# bela_expansion_card_2.net
KiCad netlist of a schematic drawn in Altium Designer
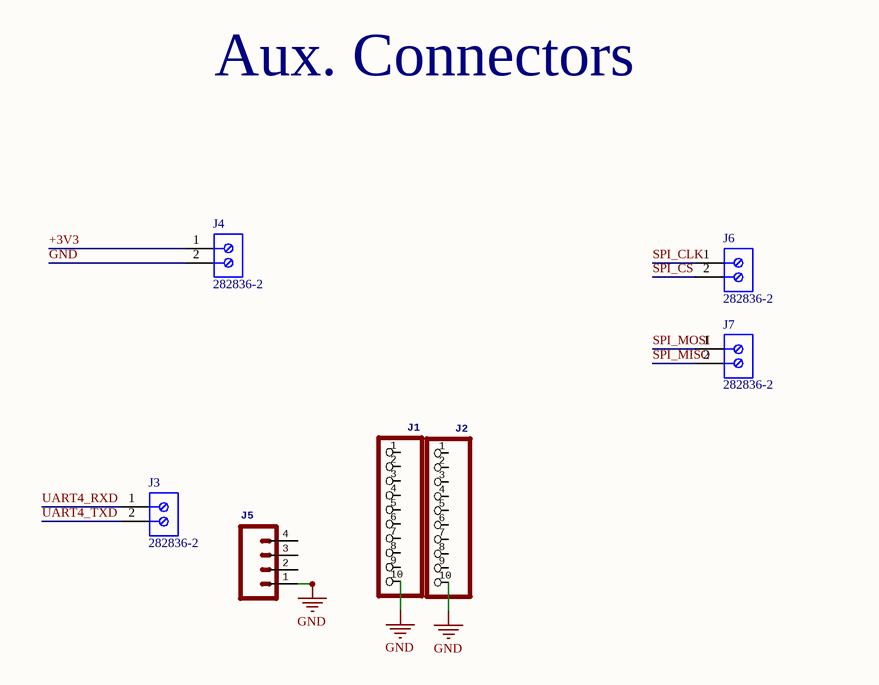
[diagram p0: bela_expansion_card_2.SchDoc]

(export (version "E")
  (design (tool "Eeschema 10.0.6"))
  (components
    (comp (ref "J1")
      (value "PINHD-1X10")
      (footprint "HDR1X10")
      (description "PIN HEADER")
      (fields (field (name "LIBRARYNAME") "pinhead"))
      (libsource (lib "pinhead") (part "PINHD-1X10"))
    )
    (comp (ref "J2")
      (value "PINHD-1X10")
      (footprint "HDR1X10")
      (description "PIN HEADER")
      (fields (field (name "LIBRARYNAME") "pinhead"))
      (libsource (lib "Miscellaneous Connectors") (part "PINHD-1X10"))
    )
    (comp (ref "J3")
      (value "282836-2")
      (footprint "TECO-282836-2_V")
      (description "Female Header, Pitch 5 mm, 1 x 2 Position, Height 10 mm, Tail Length 3.5 mm, Rohs, Bulk")
      (fields (field (name "VOLTAGE") "300V") (field (name "MANUFACTURER") "TE Connectivity"))
      (libsource (lib "Altium Content Vault") (part "CN-1P-F-TB2"))
    )
    (comp (ref "J4")
      (value "282836-2")
      (footprint "TECO-282836-2_V")
      (description "Female Header, Pitch 5 mm, 1 x 2 Position, Height 10 mm, Tail Length 3.5 mm, Rohs, Bulk")
      (fields (field (name "VOLTAGE") "300V") (field (name "MANUFACTURER") "TE Connectivity"))
      (libsource (lib "Altium Content Vault") (part "CN-1P-F-TB2"))
    )
    (comp (ref "J5")
      (value "M04PTH")
      (footprint "1X04")
      (libsource (lib "SparkFun-Connectors") (part "M04PTH"))
    )
    (comp (ref "J6")
      (value "282836-2")
      (footprint "TECO-282836-2_V")
      (description "Female Header, Pitch 5 mm, 1 x 2 Position, Height 10 mm, Tail Length 3.5 mm, Rohs, Bulk")
      (fields (field (name "VOLTAGE") "300V") (field (name "MANUFACTURER") "TE Connectivity"))
      (libsource (lib "Altium Content Vault") (part "CN-1P-F-TB2"))
    )
    (comp (ref "J7")
      (value "282836-2")
      (footprint "TECO-282836-2_V")
      (description "Female Header, Pitch 5 mm, 1 x 2 Position, Height 10 mm, Tail Length 3.5 mm, Rohs, Bulk")
      (fields (field (name "VOLTAGE") "300V") (field (name "MANUFACTURER") "TE Connectivity"))
      (libsource (lib "Altium Content Vault") (part "CN-1P-F-TB2"))
    )
  )
  (nets
    (net (code "1") (name "/+3V3") (class "Default")
      (node (ref "J4") (pin "1") (pinfunction "1_1") (pintype "passive"))
    )
    (net (code "2") (name "/SPI_CLK") (class "Default")
      (node (ref "J6") (pin "1") (pinfunction "1_1") (pintype "passive"))
    )
    (net (code "3") (name "/SPI_CS") (class "Default")
      (node (ref "J6") (pin "2") (pinfunction "2_2") (pintype "passive"))
    )
    (net (code "4") (name "/SPI_MISO") (class "Default")
      (node (ref "J7") (pin "2") (pinfunction "2_2") (pintype "passive"))
    )
    (net (code "5") (name "/SPI_MOSI") (class "Default")
      (node (ref "J7") (pin "1") (pinfunction "1_1") (pintype "passive"))
    )
    (net (code "6") (name "/UART4_RXD") (class "Default")
      (node (ref "J3") (pin "1") (pinfunction "1_1") (pintype "passive"))
    )
    (net (code "7") (name "/UART4_TXD") (class "Default")
      (node (ref "J3") (pin "2") (pinfunction "2_2") (pintype "passive"))
    )
    (net (code "8") (name "GND") (class "Default")
      (node (ref "J1") (pin "10") (pinfunction "10_10") (pintype "passive"))
      (node (ref "J2") (pin "10") (pinfunction "10_10") (pintype "passive"))
      (node (ref "J4") (pin "2") (pinfunction "2_2") (pintype "passive"))
      (node (ref "J5") (pin "1") (pinfunction "1_1") (pintype "passive"))
    )
    (net (code "9") (name "unconnected-(J1-Pad1)") (class "Default")
      (node (ref "J1") (pin "1") (pinfunction "1_1") (pintype "passive"))
    )
    (net (code "10") (name "unconnected-(J1-Pad2)") (class "Default")
      (node (ref "J1") (pin "2") (pinfunction "2_2") (pintype "passive"))
    )
    (net (code "11") (name "unconnected-(J1-Pad3)") (class "Default")
      (node (ref "J1") (pin "3") (pinfunction "3_3") (pintype "passive"))
    )
    (net (code "12") (name "unconnected-(J1-Pad4)") (class "Default")
      (node (ref "J1") (pin "4") (pinfunction "4_4") (pintype "passive"))
    )
    (net (code "13") (name "unconnected-(J1-Pad5)") (class "Default")
      (node (ref "J1") (pin "5") (pinfunction "5_5") (pintype "passive"))
    )
    (net (code "14") (name "unconnected-(J1-Pad6)") (class "Default")
      (node (ref "J1") (pin "6") (pinfunction "6_6") (pintype "passive"))
    )
    (net (code "15") (name "unconnected-(J1-Pad7)") (class "Default")
      (node (ref "J1") (pin "7") (pinfunction "7_7") (pintype "passive"))
    )
    (net (code "16") (name "unconnected-(J1-Pad8)") (class "Default")
      (node (ref "J1") (pin "8") (pinfunction "8_8") (pintype "passive"))
    )
    (net (code "17") (name "unconnected-(J1-Pad9)") (class "Default")
      (node (ref "J1") (pin "9") (pinfunction "9_9") (pintype "passive"))
    )
    (net (code "18") (name "unconnected-(J2-Pad1)") (class "Default")
      (node (ref "J2") (pin "1") (pinfunction "1_1") (pintype "passive"))
    )
    (net (code "19") (name "unconnected-(J2-Pad2)") (class "Default")
      (node (ref "J2") (pin "2") (pinfunction "2_2") (pintype "passive"))
    )
    (net (code "20") (name "unconnected-(J2-Pad3)") (class "Default")
      (node (ref "J2") (pin "3") (pinfunction "3_3") (pintype "passive"))
    )
    (net (code "21") (name "unconnected-(J2-Pad4)") (class "Default")
      (node (ref "J2") (pin "4") (pinfunction "4_4") (pintype "passive"))
    )
    (net (code "22") (name "unconnected-(J2-Pad5)") (class "Default")
      (node (ref "J2") (pin "5") (pinfunction "5_5") (pintype "passive"))
    )
    (net (code "23") (name "unconnected-(J2-Pad6)") (class "Default")
      (node (ref "J2") (pin "6") (pinfunction "6_6") (pintype "passive"))
    )
    (net (code "24") (name "unconnected-(J2-Pad7)") (class "Default")
      (node (ref "J2") (pin "7") (pinfunction "7_7") (pintype "passive"))
    )
    (net (code "25") (name "unconnected-(J2-Pad8)") (class "Default")
      (node (ref "J2") (pin "8") (pinfunction "8_8") (pintype "passive"))
    )
    (net (code "26") (name "unconnected-(J2-Pad9)") (class "Default")
      (node (ref "J2") (pin "9") (pinfunction "9_9") (pintype "passive"))
    )
    (net (code "27") (name "unconnected-(J5-Pad2)") (class "Default")
      (node (ref "J5") (pin "2") (pinfunction "2_2") (pintype "passive"))
    )
    (net (code "28") (name "unconnected-(J5-Pad3)") (class "Default")
      (node (ref "J5") (pin "3") (pinfunction "3_3") (pintype "passive"))
    )
    (net (code "29") (name "unconnected-(J5-Pad4)") (class "Default")
      (node (ref "J5") (pin "4") (pinfunction "4_4") (pintype "passive"))
    )
  )
)
